# AudioAY.net
KiCad netlist of a schematic drawn in Altium Designer
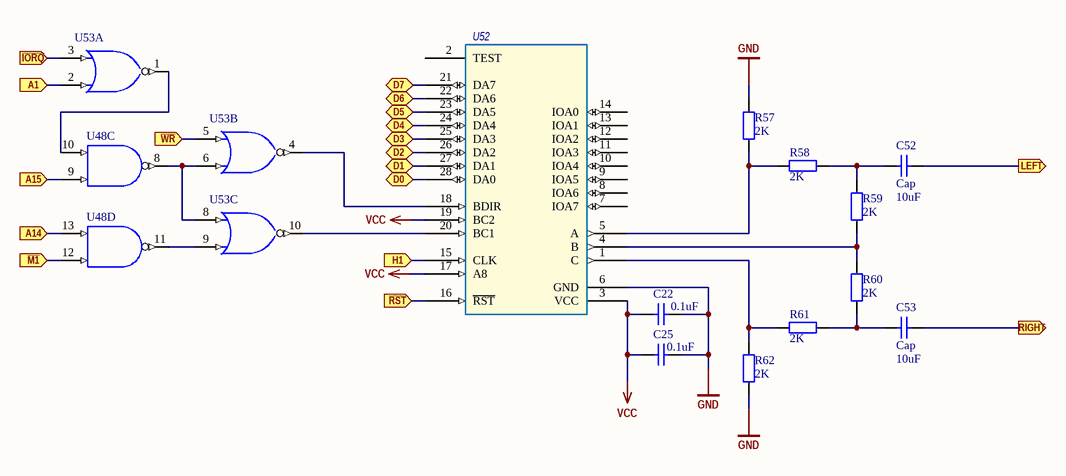
[diagram p0: AudioAY.SchDoc]

(export (version "E")
  (design (tool "Eeschema 10.0.6"))
  (components
    (comp (ref "C22")
      (value "0.1uF")
      (footprint "RAD-0.3")
      (description "Capacitor")
      (fields (field (name "Comment") "Cap") (field (name "PUBLISHER") "Altium Limited"))
      (libsource (lib "Lenin") (part "Cap"))
    )
    (comp (ref "C25")
      (value "0.1uF")
      (footprint "RAD-0.3")
      (description "Capacitor")
      (fields (field (name "Comment") "Cap") (field (name "PUBLISHER") "Altium Limited"))
      (libsource (lib "Lenin") (part "Cap"))
    )
    (comp (ref "C52")
      (value "Cap")
      (footprint "RAD-0.3")
      (description "Capacitor")
      (fields (field (name "ALTIUM_VALUE") "10uF") (field (name "PUBLISHER") "Altium Limited"))
      (libsource (lib "Lenin") (part "Cap"))
    )
    (comp (ref "C53")
      (value "Cap")
      (footprint "RAD-0.3")
      (description "Capacitor")
      (fields (field (name "ALTIUM_VALUE") "10uF") (field (name "PUBLISHER") "Altium Limited"))
      (libsource (lib "Lenin") (part "Cap"))
    )
    (comp (ref "R57")
      (value "2K")
      (footprint "Lenin:AXIAL-0.4")
      (description "Resistor")
      (fields (field (name "Comment") "Res2") (field (name "PUBLISHER") "Altium Limited"))
      (libsource (lib "") (part "Res2_1"))
    )
    (comp (ref "R58")
      (value "2K")
      (footprint "Lenin:AXIAL-0.4")
      (description "Resistor")
      (fields (field (name "Comment") "Res2") (field (name "PUBLISHER") "Altium Limited"))
      (libsource (lib "Lenin") (part "Res2"))
    )
    (comp (ref "R59")
      (value "2K")
      (footprint "Lenin:AXIAL-0.4")
      (description "Resistor")
      (fields (field (name "Comment") "Res2") (field (name "PUBLISHER") "Altium Limited"))
      (libsource (lib "") (part "Res2_1"))
    )
    (comp (ref "R60")
      (value "2K")
      (footprint "Lenin:AXIAL-0.4")
      (description "Resistor")
      (fields (field (name "Comment") "Res2") (field (name "PUBLISHER") "Altium Limited"))
      (libsource (lib "") (part "Res2_1"))
    )
    (comp (ref "R61")
      (value "2K")
      (footprint "Lenin:AXIAL-0.4")
      (description "Resistor")
      (fields (field (name "Comment") "Res2") (field (name "PUBLISHER") "Altium Limited"))
      (libsource (lib "Lenin") (part "Res2"))
    )
    (comp (ref "R62")
      (value "2K")
      (footprint "Lenin:AXIAL-0.4")
      (description "Resistor")
      (fields (field (name "Comment") "Res2") (field (name "PUBLISHER") "Altium Limited"))
      (libsource (lib "") (part "Res2_1"))
    )
    (comp (ref "U48")
      (value "SN74HC00N")
      (footprint "N014")
      (description "Quadruple 2-Input Positive-NAND Gate")
      (fields (field (name "PUBLISHER") "Altium Limited"))
      (libsource (lib "TI Logic Gate 2") (part "SN74HC00N"))
    )
    (comp (ref "U52")
      (value "AY-3-8912")
      (footprint "ST-Microelectronics Footprints:FDIP28W")
      (libsource (lib "Lenin") (part "AY-3-8912"))
    )
    (comp (ref "U53")
      (value "SN74HC02N")
      (footprint "N014")
      (description "Quadruple 2-Input Positive-NOR Gate")
      (fields (field (name "PUBLISHER") "Altium Limited"))
      (libsource (lib "TI Logic Gate 2") (part "SN74HC02N"))
    )
  )
  (nets
    (net (code "1") (name "/A1") (class "Default")
      (node (ref "U53") (pin "2") (pinfunction "A_2") (pintype "input"))
    )
    (net (code "2") (name "/A14") (class "Default")
      (node (ref "U48") (pin "13") (pinfunction "B_13") (pintype "input"))
    )
    (net (code "3") (name "/A15") (class "Default")
      (node (ref "U48") (pin "9") (pinfunction "A_9") (pintype "input"))
    )
    (net (code "4") (name "/D0") (class "Default")
      (node (ref "U52") (pin "28") (pinfunction "DA0_28") (pintype "bidirectional"))
    )
    (net (code "5") (name "/D1") (class "Default")
      (node (ref "U52") (pin "27") (pinfunction "DA1_27") (pintype "bidirectional"))
    )
    (net (code "6") (name "/D2") (class "Default")
      (node (ref "U52") (pin "26") (pinfunction "DA2_26") (pintype "bidirectional"))
    )
    (net (code "7") (name "/D3") (class "Default")
      (node (ref "U52") (pin "25") (pinfunction "DA3_25") (pintype "bidirectional"))
    )
    (net (code "8") (name "/D4") (class "Default")
      (node (ref "U52") (pin "24") (pinfunction "DA4_24") (pintype "bidirectional"))
    )
    (net (code "9") (name "/D5") (class "Default")
      (node (ref "U52") (pin "23") (pinfunction "DA5_23") (pintype "bidirectional"))
    )
    (net (code "10") (name "/D6") (class "Default")
      (node (ref "U52") (pin "22") (pinfunction "DA6_22") (pintype "bidirectional"))
    )
    (net (code "11") (name "/D7") (class "Default")
      (node (ref "U52") (pin "21") (pinfunction "DA7_21") (pintype "bidirectional"))
    )
    (net (code "12") (name "/H1") (class "Default")
      (node (ref "U52") (pin "15") (pinfunction "CLK_15") (pintype "input"))
    )
    (net (code "13") (name "/LEFT") (class "Default")
      (node (ref "C52") (pin "2") (pinfunction "2_2") (pintype "passive"))
    )
    (net (code "14") (name "/RIGHT") (class "Default")
      (node (ref "C53") (pin "2") (pinfunction "2_2") (pintype "passive"))
    )
    (net (code "15") (name "/~{IORQ}") (class "Default")
      (node (ref "U53") (pin "3") (pinfunction "B_3") (pintype "input"))
    )
    (net (code "16") (name "/~{M1}") (class "Default")
      (node (ref "U48") (pin "12") (pinfunction "A_12") (pintype "input"))
    )
    (net (code "17") (name "/~{RST}") (class "Default")
      (node (ref "U52") (pin "16") (pinfunction "~{RST}_16") (pintype "input"))
    )
    (net (code "18") (name "/~{WR}") (class "Default")
      (node (ref "U53") (pin "5") (pinfunction "A_5") (pintype "input"))
    )
    (net (code "19") (name "GND") (class "Default")
      (node (ref "C22") (pin "2") (pinfunction "2_2") (pintype "passive"))
      (node (ref "C25") (pin "2") (pinfunction "2_2") (pintype "passive"))
      (node (ref "R57") (pin "2") (pinfunction "2_2") (pintype "passive"))
      (node (ref "R62") (pin "1") (pinfunction "1_1") (pintype "passive"))
      (node (ref "U48") (pin "7") (pinfunction "GND_7") (pintype "power_in"))
      (node (ref "U52") (pin "6") (pinfunction "GND_6") (pintype "power_in"))
      (node (ref "U53") (pin "7") (pinfunction "GND_7") (pintype "power_in"))
    )
    (net (code "20") (name "Net-(C52-Pad1)") (class "Default")
      (node (ref "C52") (pin "1") (pinfunction "1_1") (pintype "passive"))
      (node (ref "R58") (pin "2") (pinfunction "2_2") (pintype "passive"))
      (node (ref "R59") (pin "2") (pinfunction "2_2") (pintype "passive"))
    )
    (net (code "21") (name "Net-(C53-Pad1)") (class "Default")
      (node (ref "C53") (pin "1") (pinfunction "1_1") (pintype "passive"))
      (node (ref "R60") (pin "1") (pinfunction "1_1") (pintype "passive"))
      (node (ref "R61") (pin "2") (pinfunction "2_2") (pintype "passive"))
    )
    (net (code "22") (name "Net-(U48C-B)") (class "Default")
      (node (ref "U48") (pin "10") (pinfunction "B_10") (pintype "input"))
      (node (ref "U53") (pin "1") (pinfunction "Y_1") (pintype "output"))
    )
    (net (code "23") (name "Net-(U48C-Y)") (class "Default")
      (node (ref "U48") (pin "8") (pinfunction "Y_8") (pintype "output"))
      (node (ref "U53") (pin "6") (pinfunction "B_6") (pintype "input"))
      (node (ref "U53") (pin "8") (pinfunction "A_8") (pintype "input"))
    )
    (net (code "24") (name "Net-(U48D-Y)") (class "Default")
      (node (ref "U48") (pin "11") (pinfunction "Y_11") (pintype "output"))
      (node (ref "U53") (pin "9") (pinfunction "B_9") (pintype "input"))
    )
    (net (code "25") (name "Net-(U52-A)") (class "Default")
      (node (ref "R57") (pin "1") (pinfunction "1_1") (pintype "passive"))
      (node (ref "R58") (pin "1") (pinfunction "1_1") (pintype "passive"))
      (node (ref "U52") (pin "5") (pinfunction "A_5") (pintype "output"))
    )
    (net (code "26") (name "Net-(U52-B)") (class "Default")
      (node (ref "R59") (pin "1") (pinfunction "1_1") (pintype "passive"))
      (node (ref "R60") (pin "2") (pinfunction "2_2") (pintype "passive"))
      (node (ref "U52") (pin "4") (pinfunction "B_4") (pintype "output"))
    )
    (net (code "27") (name "Net-(U52-BC1)") (class "Default")
      (node (ref "U52") (pin "20") (pinfunction "BC1_20") (pintype "input"))
      (node (ref "U53") (pin "10") (pinfunction "Y_10") (pintype "output"))
    )
    (net (code "28") (name "Net-(U52-BDIR)") (class "Default")
      (node (ref "U52") (pin "18") (pinfunction "BDIR_18") (pintype "input"))
      (node (ref "U53") (pin "4") (pinfunction "Y_4") (pintype "output"))
    )
    (net (code "29") (name "Net-(U52-C)") (class "Default")
      (node (ref "R61") (pin "1") (pinfunction "1_1") (pintype "passive"))
      (node (ref "R62") (pin "2") (pinfunction "2_2") (pintype "passive"))
      (node (ref "U52") (pin "1") (pinfunction "C_1") (pintype "output"))
    )
    (net (code "30") (name "VCC") (class "Default")
      (node (ref "C22") (pin "1") (pinfunction "1_1") (pintype "passive"))
      (node (ref "C25") (pin "1") (pinfunction "1_1") (pintype "passive"))
      (node (ref "U48") (pin "14") (pinfunction "VCC_14") (pintype "power_in"))
      (node (ref "U52") (pin "17") (pinfunction "A8_17") (pintype "input"))
      (node (ref "U52") (pin "19") (pinfunction "BC2_19") (pintype "input"))
      (node (ref "U52") (pin "3") (pinfunction "VCC_3") (pintype "power_in"))
      (node (ref "U53") (pin "14") (pinfunction "VCC_14") (pintype "power_in"))
    )
    (net (code "31") (name "unconnected-(U52-IOA0-Pad14)") (class "Default")
      (node (ref "U52") (pin "14") (pinfunction "IOA0_14") (pintype "bidirectional"))
    )
    (net (code "32") (name "unconnected-(U52-IOA1-Pad13)") (class "Default")
      (node (ref "U52") (pin "13") (pinfunction "IOA1_13") (pintype "bidirectional"))
    )
    (net (code "33") (name "unconnected-(U52-IOA2-Pad12)") (class "Default")
      (node (ref "U52") (pin "12") (pinfunction "IOA2_12") (pintype "bidirectional"))
    )
    (net (code "34") (name "unconnected-(U52-IOA3-Pad11)") (class "Default")
      (node (ref "U52") (pin "11") (pinfunction "IOA3_11") (pintype "bidirectional"))
    )
    (net (code "35") (name "unconnected-(U52-IOA4-Pad10)") (class "Default")
      (node (ref "U52") (pin "10") (pinfunction "IOA4_10") (pintype "bidirectional"))
    )
    (net (code "36") (name "unconnected-(U52-IOA5-Pad9)") (class "Default")
      (node (ref "U52") (pin "9") (pinfunction "IOA5_9") (pintype "bidirectional"))
    )
    (net (code "37") (name "unconnected-(U52-IOA6-Pad8)") (class "Default")
      (node (ref "U52") (pin "8") (pinfunction "IOA6_8") (pintype "bidirectional"))
    )
    (net (code "38") (name "unconnected-(U52-IOA7-Pad7)") (class "Default")
      (node (ref "U52") (pin "7") (pinfunction "IOA7_7") (pintype "bidirectional"))
    )
    (net (code "39") (name "unconnected-(U52-TEST-Pad2)") (class "Default")
      (node (ref "U52") (pin "2") (pinfunction "TEST_2") (pintype "passive"))
    )
  )
)
